# RS485_Breakout.net
KiCad netlist of a schematic drawn in EAGLE
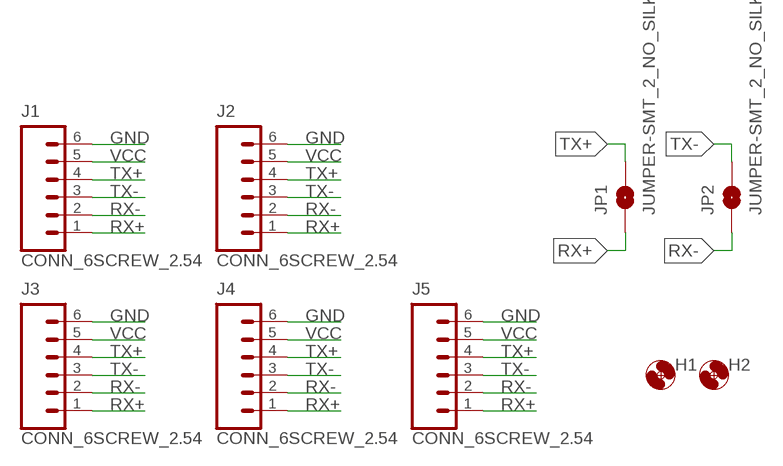
[diagram p0: schematic, sheet 1]

(export (version "E")
  (design (tool "Eeschema 10.0.6"))
  (components
    (comp (ref "H1")
      (value "MOUNTING_HOLE4_NP")
      (footprint "eagle-import:4_40")
      (libsource (lib "eagle-import") (part "MOUNTING_HOLE4_NP"))
    )
    (comp (ref "H2")
      (value "MOUNTING_HOLE4_NP")
      (footprint "eagle-import:4_40")
      (libsource (lib "eagle-import") (part "MOUNTING_HOLE4_NP"))
    )
    (comp (ref "J1")
      (value "CONN_6SCREW_2.54")
      (footprint "eagle-import:1X06_SCREW")
      (fields (field (name "MF") "OnShore") (field (name "MPN") "OSTVN06A150"))
      (libsource (lib "eagle-import") (part "CONN_6SCREW_2.54"))
    )
    (comp (ref "J2")
      (value "CONN_6SCREW_2.54")
      (footprint "eagle-import:1X06_SCREW")
      (fields (field (name "MF") "OnShore") (field (name "MPN") "OSTVN06A150"))
      (libsource (lib "eagle-import") (part "CONN_6SCREW_2.54"))
    )
    (comp (ref "J3")
      (value "CONN_6SCREW_2.54")
      (footprint "eagle-import:1X06_SCREW")
      (fields (field (name "MF") "OnShore") (field (name "MPN") "OSTVN06A150"))
      (libsource (lib "eagle-import") (part "CONN_6SCREW_2.54"))
    )
    (comp (ref "J4")
      (value "CONN_6SCREW_2.54")
      (footprint "eagle-import:1X06_SCREW")
      (fields (field (name "MF") "OnShore") (field (name "MPN") "OSTVN06A150"))
      (libsource (lib "eagle-import") (part "CONN_6SCREW_2.54"))
    )
    (comp (ref "J5")
      (value "CONN_6SCREW_2.54")
      (footprint "eagle-import:1X06_SCREW")
      (fields (field (name "MF") "OnShore") (field (name "MPN") "OSTVN06A150"))
      (libsource (lib "eagle-import") (part "CONN_6SCREW_2.54"))
    )
    (comp (ref "JP1")
      (value "JUMPER-SMT_2_NO_SILK")
      (footprint "eagle-import:SMT-JUMPER_2_NO_SILK")
      (libsource (lib "eagle-import") (part "JUMPER-SMT_2_NO_SILK"))
    )
    (comp (ref "JP2")
      (value "JUMPER-SMT_2_NO_SILK")
      (footprint "eagle-import:SMT-JUMPER_2_NO_SILK")
      (libsource (lib "eagle-import") (part "JUMPER-SMT_2_NO_SILK"))
    )
  )
  (nets
    (net (code "1") (name "/GND") (class "Default")
      (node (ref "J1") (pin "6") (pinfunction "6_6") (pintype "passive"))
      (node (ref "J2") (pin "6") (pinfunction "6_6") (pintype "passive"))
      (node (ref "J3") (pin "6") (pinfunction "6_6") (pintype "passive"))
      (node (ref "J4") (pin "6") (pinfunction "6_6") (pintype "passive"))
      (node (ref "J5") (pin "6") (pinfunction "6_6") (pintype "passive"))
    )
    (net (code "2") (name "/VCC") (class "Default")
      (node (ref "J1") (pin "5") (pinfunction "5_5") (pintype "passive"))
      (node (ref "J2") (pin "5") (pinfunction "5_5") (pintype "passive"))
      (node (ref "J3") (pin "5") (pinfunction "5_5") (pintype "passive"))
      (node (ref "J4") (pin "5") (pinfunction "5_5") (pintype "passive"))
      (node (ref "J5") (pin "5") (pinfunction "5_5") (pintype "passive"))
    )
    (net (code "3") (name "RX+") (class "Default")
      (node (ref "J1") (pin "1") (pinfunction "1_1") (pintype "passive"))
      (node (ref "J2") (pin "1") (pinfunction "1_1") (pintype "passive"))
      (node (ref "J3") (pin "1") (pinfunction "1_1") (pintype "passive"))
      (node (ref "J4") (pin "1") (pinfunction "1_1") (pintype "passive"))
      (node (ref "J5") (pin "1") (pinfunction "1_1") (pintype "passive"))
      (node (ref "JP1") (pin "1") (pinfunction "1_1") (pintype "passive"))
    )
    (net (code "4") (name "RX-") (class "Default")
      (node (ref "J1") (pin "2") (pinfunction "2_2") (pintype "passive"))
      (node (ref "J2") (pin "2") (pinfunction "2_2") (pintype "passive"))
      (node (ref "J3") (pin "2") (pinfunction "2_2") (pintype "passive"))
      (node (ref "J4") (pin "2") (pinfunction "2_2") (pintype "passive"))
      (node (ref "J5") (pin "2") (pinfunction "2_2") (pintype "passive"))
      (node (ref "JP2") (pin "1") (pinfunction "1_1") (pintype "passive"))
    )
    (net (code "5") (name "TX+") (class "Default")
      (node (ref "J1") (pin "4") (pinfunction "4_4") (pintype "passive"))
      (node (ref "J2") (pin "4") (pinfunction "4_4") (pintype "passive"))
      (node (ref "J3") (pin "4") (pinfunction "4_4") (pintype "passive"))
      (node (ref "J4") (pin "4") (pinfunction "4_4") (pintype "passive"))
      (node (ref "J5") (pin "4") (pinfunction "4_4") (pintype "passive"))
      (node (ref "JP1") (pin "2") (pinfunction "2_2") (pintype "passive"))
    )
    (net (code "6") (name "TX-") (class "Default")
      (node (ref "J1") (pin "3") (pinfunction "3_3") (pintype "passive"))
      (node (ref "J2") (pin "3") (pinfunction "3_3") (pintype "passive"))
      (node (ref "J3") (pin "3") (pinfunction "3_3") (pintype "passive"))
      (node (ref "J4") (pin "3") (pinfunction "3_3") (pintype "passive"))
      (node (ref "J5") (pin "3") (pinfunction "3_3") (pintype "passive"))
      (node (ref "JP2") (pin "2") (pinfunction "2_2") (pintype "passive"))
    )
  )
)
